# Sheet1.net
KiCad netlist of a schematic drawn in Altium Designer
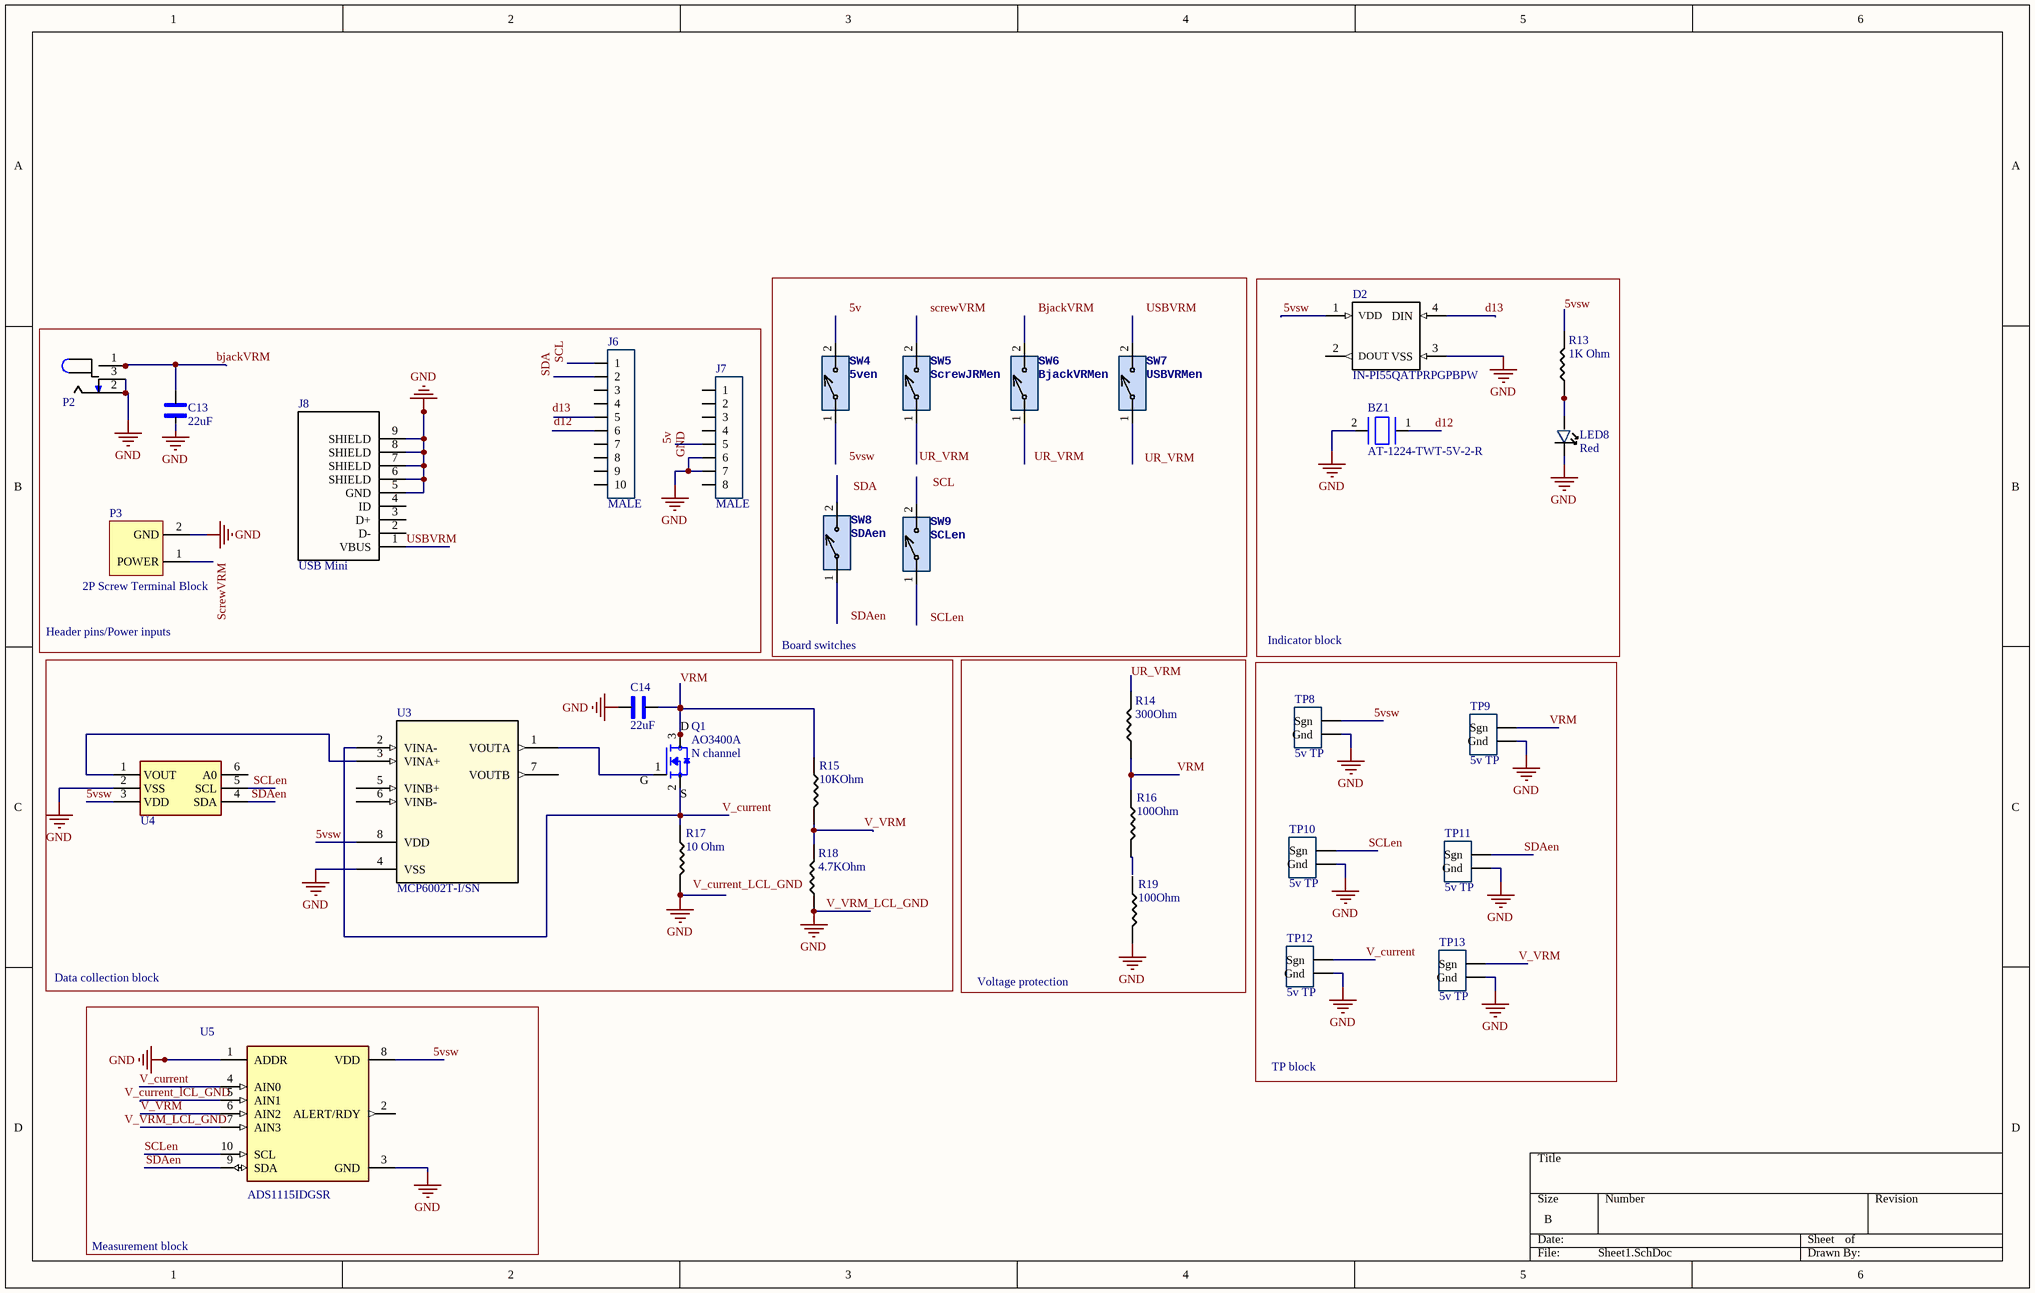
[diagram p0: Sheet1.SchDoc]

(export (version "E")
  (design (tool "Eeschema 10.0.6"))
  (components
    (comp (ref "BZ1")
      (value "AT-1224-TWT-5V-2-R")
      (footprint "BUZZER- TH")
      (fields (field (name "MFR PART #") "AT-1224-TWT-5V-2-R"))
      (libsource (lib "ECEN5730Lib_2023_05_DS") (part "BUZZER_1"))
    )
    (comp (ref "C13")
      (value "22uF")
      (footprint "1206_Passive_Capacitor")
      (description "22uF ±10% 25V X5R 1206 Multilayer Ceramic Capacitors MLCC - SMD/SMT RoHS")
      (fields (field (name "MFR PART #") "CL31A226KAHNNNE") (field (name "LCSC PART#") "C12891"))
      (libsource (lib "ECEN5730Lib_2023_05_DS") (part "C_22uF_1206"))
    )
    (comp (ref "C14")
      (value "22uF")
      (footprint "1206_Passive_Capacitor")
      (description "22uF ±10% 25V X5R 1206 Multilayer Ceramic Capacitors MLCC - SMD/SMT RoHS")
      (fields (field (name "MFR PART #") "CL31A226KAHNNNE") (field (name "LCSC PART#") "C12891"))
      (libsource (lib "ECEN5730Lib_2023_05_DS") (part "C_22uF_1206"))
    )
    (comp (ref "D2")
      (value "IN-PI55QATPRPGPBPW")
      (footprint "SERIAL_LED - duplicate")
      (fields
        (field (name "LCSC PART#") "C2843785")
        (field (name "MFR PART #") "XL-5050RGBC-WS2812B")
        (field (name "MANUFACTURER") "XINGLIGHT")
      )
      (libsource (lib "ECEN5730Lib_2023_05_DS") (part "LED_Smart"))
    )
    (comp (ref "J6")
      (value "MALE")
      (footprint "10_PIN_100MIL-Male")
      (description "Pin Header 10 1 Straight ，180degrees 2.54mm Through Hole,P=2.54mm Pin Header & Female Header RoHS")
      (fields (field (name "LCSC PART#") "C124372") (field (name "Comment") "MALE 10PIN"))
      (libsource (lib "ECEN5730Lib_2023_05_DS") (part "JM_10_PIN_MALE"))
    )
    (comp (ref "J7")
      (value "MALE")
      (footprint "8_PIN_100MIL-Male")
      (description "Pin Header 8 1 right-angle，180degrees 2.54mm Through Hole,P=2.54mm Pin Header & Female Header RoHS")
      (fields (field (name "LCSC PART#") "C492407") (field (name "Comment") "MALE 8PIN"))
      (libsource (lib "ECEN5730Lib_2023_05_DS") (part "JM_8_PIN_MALE"))
    )
    (comp (ref "J8")
      (value "USB Mini")
      (footprint "USB_MINI_B")
      (description "Through Hole USB Connectors RoHS")
      (fields (field (name "LCSC PART#") "C46398") (field (name "MFR PART #") "920-462A2021D10102"))
      (libsource (lib "ECEN5730Lib_2023_05_DS") (part "J_USB_B_Mini"))
    )
    (comp (ref "LED8")
      (value "Red")
      (footprint "LED_1206")
      (description "Red 621~631nm 1206 Light Emitting Diodes (LED) RoHS")
      (fields (field (name "MFR PART #") "15-21/R6C-FQ1R1B/2T") (field (name "LCSC PART#") "C93133"))
      (libsource (lib "ECEN5730Lib_2023_05_DS") (part "LED_RED_1206"))
    )
    (comp (ref "P2")
      (value "Power Jack")
      (footprint "Power_Jack")
      (description "Power Barrel Connector Jack 2.10mm ID (0.083\"), 5.50mm OD (0.217\") Through Hole, Right Angle")
      (fields (field (name "MFR PART #") "PJ-102A") (field (name "LCSC PART#") "C136744"))
      (libsource (lib "ECEN5730Lib_2023_05_DS") (part "P_Power Jack"))
    )
    (comp (ref "P3")
      (value "2P Screw Terminal Block")
      (footprint "P_Terminal block 3.5mm-pitch")
      (description "Green Straight pin 3.5mm  pitch; P=3.5mm  Screw terminal ROHS")
      (fields (field (name "MFR PART #") "KF350-3.5-2P") (field (name "MANUFACTURER") "Cixi Kefa Elec"))
      (libsource (lib "ECEN5730Lib_2023_05_DS") (part "P_Terminal block"))
    )
    (comp (ref "Q1")
      (value "AO3400A")
      (footprint "N-MOSFET")
      (description "MOSFET N Trench 30V 5.7A 1.5V @ 250uA 26.5 m? @ 5.7A,10V SOT-23-3L RoHS")
      (fields (field (name "LCSC PART#") "C20917") (field (name "ALTIUM_VALUE") "N channel"))
      (libsource (lib "ECEN5730Lib_2023_05_DS") (part "Q_Nch_MOSFET"))
    )
    (comp (ref "R13")
      (value "1K Ohm")
      (footprint "1206_Passive_Resitor")
      (description "CHIP RESISTOR - SURFACE MOUNT 1KOHMS ±1% 1/4W 1206 ROHS")
      (fields (field (name "MFR PART #") "RNCP1206FTD1K00CT") (field (name "LCSC PART#") "C4410"))
      (libsource (lib "ECEN5730Lib_2023_05_DS") (part "R_1K_1206"))
    )
    (comp (ref "R14")
      (value "300Ohm")
      (footprint "1206_Passive_Resitor")
      (description "CHIP RESISTOR - SURFACE MOUNT 300OHMS ±1% 1/4W 1206 ROHS")
      (fields (field (name "MFR PART #") "1206W4F3000T5E") (field (name "LCSC PART#") "C17887"))
      (libsource (lib "ECEN5730Lib_2023_05_DS") (part "R_300Ohm_1206"))
    )
    (comp (ref "R15")
      (value "10KOhm")
      (footprint "1206_Passive_Resitor")
      (description "10 kOhms ±5% 0.25W, 1/4W Chip Resistor 1206 (3216 Metric) Automotive AEC-Q200 Thick Film")
      (fields (field (name "MFR PART #") "RMCF1206FT10K0") (field (name "LCSC PART#") "C17902"))
      (libsource (lib "ECEN5730Lib_2023_05_DS") (part "R_10KOhm_1206"))
    )
    (comp (ref "R16")
      (value "100Ohm")
      (footprint "1206_Passive_Resitor")
      (description "100Ω ±1% 0.25W ±100ppm/℃ 1206 Chip Resistor - Surface Mount RoHS")
      (fields (field (name "LCSC PART#") "C17901") (field (name "MFR PART #") "1206W4F1000T5E"))
      (libsource (lib "ECEN5730Lib_2023_05_DS") (part "R_100Ohm_1206"))
    )
    (comp (ref "R17")
      (value "10 Ohm")
      (footprint "1206_Passive_Resitor")
      (description "CHIP RESISTOR - SURFACE MOUNT 0.1OHMS ±1% 1/4W 1206 ROHS")
      (fields (field (name "MFR PART #") "1206W4F100JT5E") (field (name "LCSC PART#") "C17903"))
      (libsource (lib "ECEN5730Lib_2023_05_DS") (part "R_10Ohm_1206"))
    )
    (comp (ref "R18")
      (value "4.7KOhm")
      (footprint "1206_Passive_Resitor")
      (description "4.7kΩ ±1% 0.25W ±100ppm/℃ 1206 Chip Resistor - Surface Mount RoHS")
      (fields (field (name "LCSC PART#") "C17936") (field (name "MFR PART #") "1206W4F4701T5E"))
      (libsource (lib "ECEN5730Lib_2023_05_DS") (part "R_4.7k_1206"))
    )
    (comp (ref "R19")
      (value "100Ohm")
      (footprint "1206_Passive_Resitor")
      (description "100Ω ±1% 0.25W ±100ppm/℃ 1206 Chip Resistor - Surface Mount RoHS")
      (fields (field (name "LCSC PART#") "C17901") (field (name "MFR PART #") "1206W4F1000T5E"))
      (libsource (lib "ECEN5730Lib_2023_05_DS") (part "R_100Ohm_1206"))
    )
    (comp (ref "SW4")
      (value "5ven")
      (footprint "2Pin-Header-Conn")
      (description "2Pin Header")
      (fields (field (name "LCSC PART#") "C124375"))
      (libsource (lib "ECEN5730Lib_2023_05_DS") (part "SW_2Pin_100mil_Switch"))
    )
    (comp (ref "SW5")
      (value "ScrewJRMen")
      (footprint "2Pin-Header-Conn")
      (description "2Pin Header")
      (fields (field (name "LCSC PART#") "C124375"))
      (libsource (lib "ECEN5730Lib_2023_05_DS") (part "SW_2Pin_100mil_Switch"))
    )
    (comp (ref "SW6")
      (value "BjackVRMen")
      (footprint "2Pin-Header-Conn")
      (description "2Pin Header")
      (fields (field (name "LCSC PART#") "C124375"))
      (libsource (lib "ECEN5730Lib_2023_05_DS") (part "SW_2Pin_100mil_Switch"))
    )
    (comp (ref "SW7")
      (value "USBVRMen")
      (footprint "2Pin-Header-Conn")
      (description "2Pin Header")
      (fields (field (name "LCSC PART#") "C124375"))
      (libsource (lib "ECEN5730Lib_2023_05_DS") (part "SW_2Pin_100mil_Switch"))
    )
    (comp (ref "SW8")
      (value "SDAen")
      (footprint "2Pin-Header-Conn")
      (description "2Pin Header")
      (fields (field (name "LCSC PART#") "C124375"))
      (libsource (lib "ECEN5730Lib_2023_05_DS") (part "SW_2Pin_100mil_Switch"))
    )
    (comp (ref "SW9")
      (value "SCLen")
      (footprint "2Pin-Header-Conn")
      (description "2Pin Header")
      (fields (field (name "LCSC PART#") "C124375"))
      (libsource (lib "ECEN5730Lib_2023_05_DS") (part "SW_2Pin_100mil_Switch"))
    )
    (comp (ref "TP8")
      (value "5v TP")
      (footprint "TP10x_Probe")
      (description "Test Point 300 mil centers")
      (libsource (lib "ECEN5730Lib_2023_05_DS") (part "TP_10x_Probe"))
    )
    (comp (ref "TP9")
      (value "5v TP")
      (footprint "TP10x_Probe")
      (description "Test Point 300 mil centers")
      (libsource (lib "ECEN5730Lib_2023_05_DS") (part "TP_10x_Probe"))
    )
    (comp (ref "TP10")
      (value "5v TP")
      (footprint "TP10x_Probe")
      (description "Test Point 300 mil centers")
      (libsource (lib "ECEN5730Lib_2023_05_DS") (part "TP_10x_Probe"))
    )
    (comp (ref "TP11")
      (value "5v TP")
      (footprint "TP10x_Probe")
      (description "Test Point 300 mil centers")
      (libsource (lib "ECEN5730Lib_2023_05_DS") (part "TP_10x_Probe"))
    )
    (comp (ref "TP12")
      (value "5v TP")
      (footprint "TP10x_Probe")
      (description "Test Point 300 mil centers")
      (libsource (lib "ECEN5730Lib_2023_05_DS") (part "TP_10x_Probe"))
    )
    (comp (ref "TP13")
      (value "5v TP")
      (footprint "TP10x_Probe")
      (description "Test Point 300 mil centers")
      (libsource (lib "ECEN5730Lib_2023_05_DS") (part "TP_10x_Probe"))
    )
    (comp (ref "U3")
      (value "MCP6002T-I/SN")
      (footprint "SOIC127P600X175-8N")
      (description "0.6 V/us 2 1MHz 1.8V ~ 6V 100μA General Purpose SOIC-8_150mil  Operational Amplifier ROHS")
      (fields (field (name "MFR") "Microchip") (field (name "LCSC PART#") "C7377"))
      (libsource (lib "ECEN5730Lib_2023_05_DS") (part "U_MCP6002T-I/SN"))
    )
    (comp (ref "U4")
      (value "DAC IC")
      (footprint "MCP4725")
      (description "IC DAC 12BIT V-OUT SOT23-6")
      (fields (field (name "LCSC PART#") "C144198") (field (name "MFR PART #") "MCP4725A0T-E/CH"))
      (libsource (lib "ECEN5730Lib_2023_05_DS") (part "U_MCP4725A0T-E/CH"))
    )
    (comp (ref "U5")
      (value "ADS1115IDGSR")
      (footprint "ADC_ADS1115IDGSR")
      (description "16-Bit ADC with Integrated MUX, PGA, Comparator, Oscillator, and Reference 10-VSSOP -40 to 125")
      (fields (field (name "LCSC PART#") "C37593"))
      (libsource (lib "ECEN5730Lib_2023_05_DS") (part "U_ADC_ADS1115IDGSR"))
    )
  )
  (nets
    (net (code "1") (name "/5v") (class "Default")
      (node (ref "J7") (pin "5") (pinfunction "5_5") (pintype "passive"))
    )
    (net (code "2") (name "/5vsw") (class "Default")
      (node (ref "D2") (pin "1") (pinfunction "VDD_1") (pintype "input"))
      (node (ref "R13") (pin "2") (pinfunction "2_2") (pintype "passive"))
      (node (ref "TP8") (pin "1") (pinfunction "Sgn_1") (pintype "passive"))
      (node (ref "U3") (pin "8") (pinfunction "VDD_8") (pintype "passive"))
      (node (ref "U4") (pin "3") (pinfunction "VDD_3") (pintype "passive"))
      (node (ref "U5") (pin "8") (pinfunction "VDD_8") (pintype "power_in"))
    )
    (net (code "4") (name "/SCL") (class "Default")
      (node (ref "J6") (pin "1") (pinfunction "1_1") (pintype "passive"))
    )
    (net (code "5") (name "/SCLen") (class "Default")
      (node (ref "TP10") (pin "1") (pinfunction "Sgn_1") (pintype "passive"))
      (node (ref "U4") (pin "5") (pinfunction "SCL_5") (pintype "passive"))
      (node (ref "U5") (pin "10") (pinfunction "SCL_10") (pintype "input"))
    )
    (net (code "6") (name "/SDA") (class "Default")
      (node (ref "J6") (pin "2") (pinfunction "2_2") (pintype "passive"))
    )
    (net (code "7") (name "/SDAen") (class "Default")
      (node (ref "TP11") (pin "1") (pinfunction "Sgn_1") (pintype "passive"))
      (node (ref "U4") (pin "4") (pinfunction "SDA_4") (pintype "passive"))
      (node (ref "U5") (pin "9") (pinfunction "SDA_9") (pintype "bidirectional"))
    )
    (net (code "8") (name "/ScrewVRM") (class "Default")
      (node (ref "P3") (pin "1") (pinfunction "POWER_1") (pintype "passive"))
    )
    (net (code "9") (name "/UR_VRM") (class "Default")
      (node (ref "R14") (pin "2") (pinfunction "2_2") (pintype "passive"))
    )
    (net (code "10") (name "/USBVRM") (class "Default")
      (node (ref "J8") (pin "1") (pinfunction "VBUS_1") (pintype "passive"))
    )
    (net (code "11") (name "/VRM") (class "Default")
      (node (ref "C14") (pin "1") (pinfunction "1_1") (pintype "passive"))
      (node (ref "Q1") (pin "3") (pinfunction "D_3") (pintype "passive"))
      (node (ref "R14") (pin "1") (pinfunction "1_1") (pintype "passive"))
      (node (ref "R15") (pin "1") (pinfunction "1_1") (pintype "passive"))
      (node (ref "R16") (pin "1") (pinfunction "1_1") (pintype "passive"))
      (node (ref "TP9") (pin "1") (pinfunction "Sgn_1") (pintype "passive"))
    )
    (net (code "12") (name "/V_VRM") (class "Default")
      (node (ref "R15") (pin "2") (pinfunction "2_2") (pintype "passive"))
      (node (ref "R18") (pin "2") (pinfunction "2_2") (pintype "passive"))
      (node (ref "TP13") (pin "1") (pinfunction "Sgn_1") (pintype "passive"))
      (node (ref "U5") (pin "6") (pinfunction "AIN2_6") (pintype "input"))
    )
    (net (code "13") (name "/V_current") (class "Default")
      (node (ref "Q1") (pin "2") (pinfunction "S_2") (pintype "passive"))
      (node (ref "R17") (pin "1") (pinfunction "1_1") (pintype "passive"))
      (node (ref "TP12") (pin "1") (pinfunction "Sgn_1") (pintype "passive"))
      (node (ref "U3") (pin "2") (pinfunction "VINA-_2") (pintype "input"))
      (node (ref "U5") (pin "4") (pinfunction "AIN0_4") (pintype "input"))
    )
    (net (code "16") (name "/bjackVRM") (class "Default")
      (node (ref "C13") (pin "2") (pinfunction "2_2") (pintype "passive"))
      (node (ref "P2") (pin "1") (pinfunction "1_1") (pintype "power_in"))
    )
    (net (code "17") (name "/d12") (class "Default")
      (node (ref "BZ1") (pin "1") (pinfunction "BZ1_1") (pintype "passive"))
    )
    (net (code "18") (name "/d13") (class "Default")
      (node (ref "D2") (pin "4") (pinfunction "DIN_4") (pintype "input"))
    )
    (net (code "20") (name "GND") (class "Default")
      (node (ref "BZ1") (pin "2") (pinfunction "BZ2_2") (pintype "passive"))
      (node (ref "C13") (pin "1") (pinfunction "1_1") (pintype "passive"))
      (node (ref "C14") (pin "2") (pinfunction "2_2") (pintype "passive"))
      (node (ref "D2") (pin "3") (pinfunction "VSS_3") (pintype "input"))
      (node (ref "J7") (pin "6") (pinfunction "6_6") (pintype "passive"))
      (node (ref "J7") (pin "7") (pinfunction "7_7") (pintype "passive"))
      (node (ref "J8") (pin "5") (pinfunction "GND_5") (pintype "passive"))
      (node (ref "J8") (pin "6") (pinfunction "SHIELD_6") (pintype "passive"))
      (node (ref "J8") (pin "7") (pinfunction "SHIELD_7") (pintype "passive"))
      (node (ref "J8") (pin "8") (pinfunction "SHIELD_8") (pintype "passive"))
      (node (ref "J8") (pin "9") (pinfunction "SHIELD_9") (pintype "passive"))
      (node (ref "LED8") (pin "2") (pinfunction "2_2") (pintype "passive"))
      (node (ref "P2") (pin "2") (pinfunction "2_2") (pintype "power_in"))
      (node (ref "P2") (pin "3") (pinfunction "3_3") (pintype "power_in"))
      (node (ref "P3") (pin "2") (pinfunction "GND_2") (pintype "passive"))
      (node (ref "R17") (pin "2") (pinfunction "2_2") (pintype "passive"))
      (node (ref "R18") (pin "1") (pinfunction "1_1") (pintype "passive"))
      (node (ref "R19") (pin "2") (pinfunction "2_2") (pintype "passive"))
      (node (ref "TP10") (pin "2") (pinfunction "Gnd_2") (pintype "passive"))
      (node (ref "TP11") (pin "2") (pinfunction "Gnd_2") (pintype "passive"))
      (node (ref "TP12") (pin "2") (pinfunction "Gnd_2") (pintype "passive"))
      (node (ref "TP13") (pin "2") (pinfunction "Gnd_2") (pintype "passive"))
      (node (ref "TP8") (pin "2") (pinfunction "Gnd_2") (pintype "passive"))
      (node (ref "TP9") (pin "2") (pinfunction "Gnd_2") (pintype "passive"))
      (node (ref "U3") (pin "4") (pinfunction "VSS_4") (pintype "passive"))
      (node (ref "U4") (pin "2") (pinfunction "VSS_2") (pintype "passive"))
      (node (ref "U5") (pin "1") (pinfunction "ADDR_1") (pintype "passive"))
      (node (ref "U5") (pin "3") (pinfunction "GND_3") (pintype "power_in"))
    )
    (net (code "21") (name "Net-(LED8-Pad1)") (class "Default")
      (node (ref "LED8") (pin "1") (pinfunction "1_1") (pintype "passive"))
      (node (ref "R13") (pin "1") (pinfunction "1_1") (pintype "passive"))
    )
    (net (code "22") (name "Net-(Q1-G)") (class "Default")
      (node (ref "Q1") (pin "1") (pinfunction "G_1") (pintype "passive"))
      (node (ref "U3") (pin "1") (pinfunction "VOUTA_1") (pintype "output"))
    )
    (net (code "23") (name "Net-(U3-VINA+)") (class "Default")
      (node (ref "U3") (pin "3") (pinfunction "VINA+_3") (pintype "input"))
      (node (ref "U4") (pin "1") (pinfunction "VOUT_1") (pintype "passive"))
    )
    (net (code "24") (name "unconnected-(D2-DOUT-Pad2)") (class "Default")
      (node (ref "D2") (pin "2") (pinfunction "DOUT_2") (pintype "output"))
    )
    (net (code "25") (name "unconnected-(J6-Pad3)") (class "Default")
      (node (ref "J6") (pin "3") (pinfunction "3_3") (pintype "passive"))
    )
    (net (code "26") (name "unconnected-(J6-Pad4)") (class "Default")
      (node (ref "J6") (pin "4") (pinfunction "4_4") (pintype "passive"))
    )
    (net (code "27") (name "unconnected-(J6-Pad5)") (class "Default")
      (node (ref "J6") (pin "5") (pinfunction "5_5") (pintype "passive"))
    )
    (net (code "28") (name "unconnected-(J6-Pad6)") (class "Default")
      (node (ref "J6") (pin "6") (pinfunction "6_6") (pintype "passive"))
    )
    (net (code "29") (name "unconnected-(J6-Pad7)") (class "Default")
      (node (ref "J6") (pin "7") (pinfunction "7_7") (pintype "passive"))
    )
    (net (code "30") (name "unconnected-(J6-Pad8)") (class "Default")
      (node (ref "J6") (pin "8") (pinfunction "8_8") (pintype "passive"))
    )
    (net (code "31") (name "unconnected-(J6-Pad9)") (class "Default")
      (node (ref "J6") (pin "9") (pinfunction "9_9") (pintype "passive"))
    )
    (net (code "32") (name "unconnected-(J6-Pad10)") (class "Default")
      (node (ref "J6") (pin "10") (pinfunction "10_10") (pintype "passive"))
    )
    (net (code "33") (name "unconnected-(J7-Pad1)") (class "Default")
      (node (ref "J7") (pin "1") (pinfunction "1_1") (pintype "passive"))
    )
    (net (code "34") (name "unconnected-(J7-Pad2)") (class "Default")
      (node (ref "J7") (pin "2") (pinfunction "2_2") (pintype "passive"))
    )
    (net (code "35") (name "unconnected-(J7-Pad3)") (class "Default")
      (node (ref "J7") (pin "3") (pinfunction "3_3") (pintype "passive"))
    )
    (net (code "36") (name "unconnected-(J7-Pad4)") (class "Default")
      (node (ref "J7") (pin "4") (pinfunction "4_4") (pintype "passive"))
    )
    (net (code "37") (name "unconnected-(J7-Pad8)") (class "Default")
      (node (ref "J7") (pin "8") (pinfunction "8_8") (pintype "passive"))
    )
    (net (code "38") (name "unconnected-(J8-D+-Pad3)") (class "Default")
      (node (ref "J8") (pin "3") (pinfunction "D+_3") (pintype "passive"))
    )
    (net (code "39") (name "unconnected-(J8-D--Pad2)") (class "Default")
      (node (ref "J8") (pin "2") (pinfunction "D-_2") (pintype "passive"))
    )
    (net (code "40") (name "unconnected-(J8-ID-Pad4)") (class "Default")
      (node (ref "J8") (pin "4") (pinfunction "ID_4") (pintype "passive"))
    )
    (net (code "41") (name "unconnected-(R16-Pad2)") (class "Default")
      (node (ref "R16") (pin "2") (pinfunction "2_2") (pintype "passive"))
    )
    (net (code "42") (name "unconnected-(R19-Pad1)") (class "Default")
      (node (ref "R19") (pin "1") (pinfunction "1_1") (pintype "passive"))
    )
    (net (code "43") (name "unconnected-(SW4-Pad1)") (class "Default")
      (node (ref "SW4") (pin "1") (pinfunction "1_1") (pintype "passive"))
    )
    (net (code "44") (name "unconnected-(SW4-Pad2)") (class "Default")
      (node (ref "SW4") (pin "2") (pinfunction "2_2") (pintype "passive"))
    )
    (net (code "45") (name "unconnected-(SW5-Pad1)") (class "Default")
      (node (ref "SW5") (pin "1") (pinfunction "1_1") (pintype "passive"))
    )
    (net (code "46") (name "unconnected-(SW5-Pad2)") (class "Default")
      (node (ref "SW5") (pin "2") (pinfunction "2_2") (pintype "passive"))
    )
    (net (code "47") (name "unconnected-(SW6-Pad1)") (class "Default")
      (node (ref "SW6") (pin "1") (pinfunction "1_1") (pintype "passive"))
    )
    (net (code "48") (name "unconnected-(SW6-Pad2)") (class "Default")
      (node (ref "SW6") (pin "2") (pinfunction "2_2") (pintype "passive"))
    )
    (net (code "49") (name "unconnected-(SW7-Pad1)") (class "Default")
      (node (ref "SW7") (pin "1") (pinfunction "1_1") (pintype "passive"))
    )
    (net (code "50") (name "unconnected-(SW7-Pad2)") (class "Default")
      (node (ref "SW7") (pin "2") (pinfunction "2_2") (pintype "passive"))
    )
    (net (code "51") (name "unconnected-(SW8-Pad1)") (class "Default")
      (node (ref "SW8") (pin "1") (pinfunction "1_1") (pintype "passive"))
    )
    (net (code "52") (name "unconnected-(SW8-Pad2)") (class "Default")
      (node (ref "SW8") (pin "2") (pinfunction "2_2") (pintype "passive"))
    )
    (net (code "53") (name "unconnected-(SW9-Pad1)") (class "Default")
      (node (ref "SW9") (pin "1") (pinfunction "1_1") (pintype "passive"))
    )
    (net (code "54") (name "unconnected-(SW9-Pad2)") (class "Default")
      (node (ref "SW9") (pin "2") (pinfunction "2_2") (pintype "passive"))
    )
    (net (code "55") (name "unconnected-(U3-VINB+-Pad5)") (class "Default")
      (node (ref "U3") (pin "5") (pinfunction "VINB+_5") (pintype "input"))
    )
    (net (code "56") (name "unconnected-(U3-VINB--Pad6)") (class "Default")
      (node (ref "U3") (pin "6") (pinfunction "VINB-_6") (pintype "input"))
    )
    (net (code "57") (name "unconnected-(U3-VOUTB-Pad7)") (class "Default")
      (node (ref "U3") (pin "7") (pinfunction "VOUTB_7") (pintype "output"))
    )
    (net (code "58") (name "unconnected-(U4-A0-Pad6)") (class "Default")
      (node (ref "U4") (pin "6") (pinfunction "A0_6") (pintype "passive"))
    )
    (net (code "59") (name "unconnected-(U5-AIN1-Pad5)") (class "Default")
      (node (ref "U5") (pin "5") (pinfunction "AIN1_5") (pintype "input"))
    )
    (net (code "60") (name "unconnected-(U5-AIN3-Pad7)") (class "Default")
      (node (ref "U5") (pin "7") (pinfunction "AIN3_7") (pintype "input"))
    )
    (net (code "61") (name "unconnected-(U5-ALERT{slash}RDY-Pad2)") (class "Default")
      (node (ref "U5") (pin "2") (pinfunction "ALERT/RDY_2") (pintype "output"))
    )
  )
)
